# LM2678.net
KiCad netlist of a schematic drawn in Altium Designer
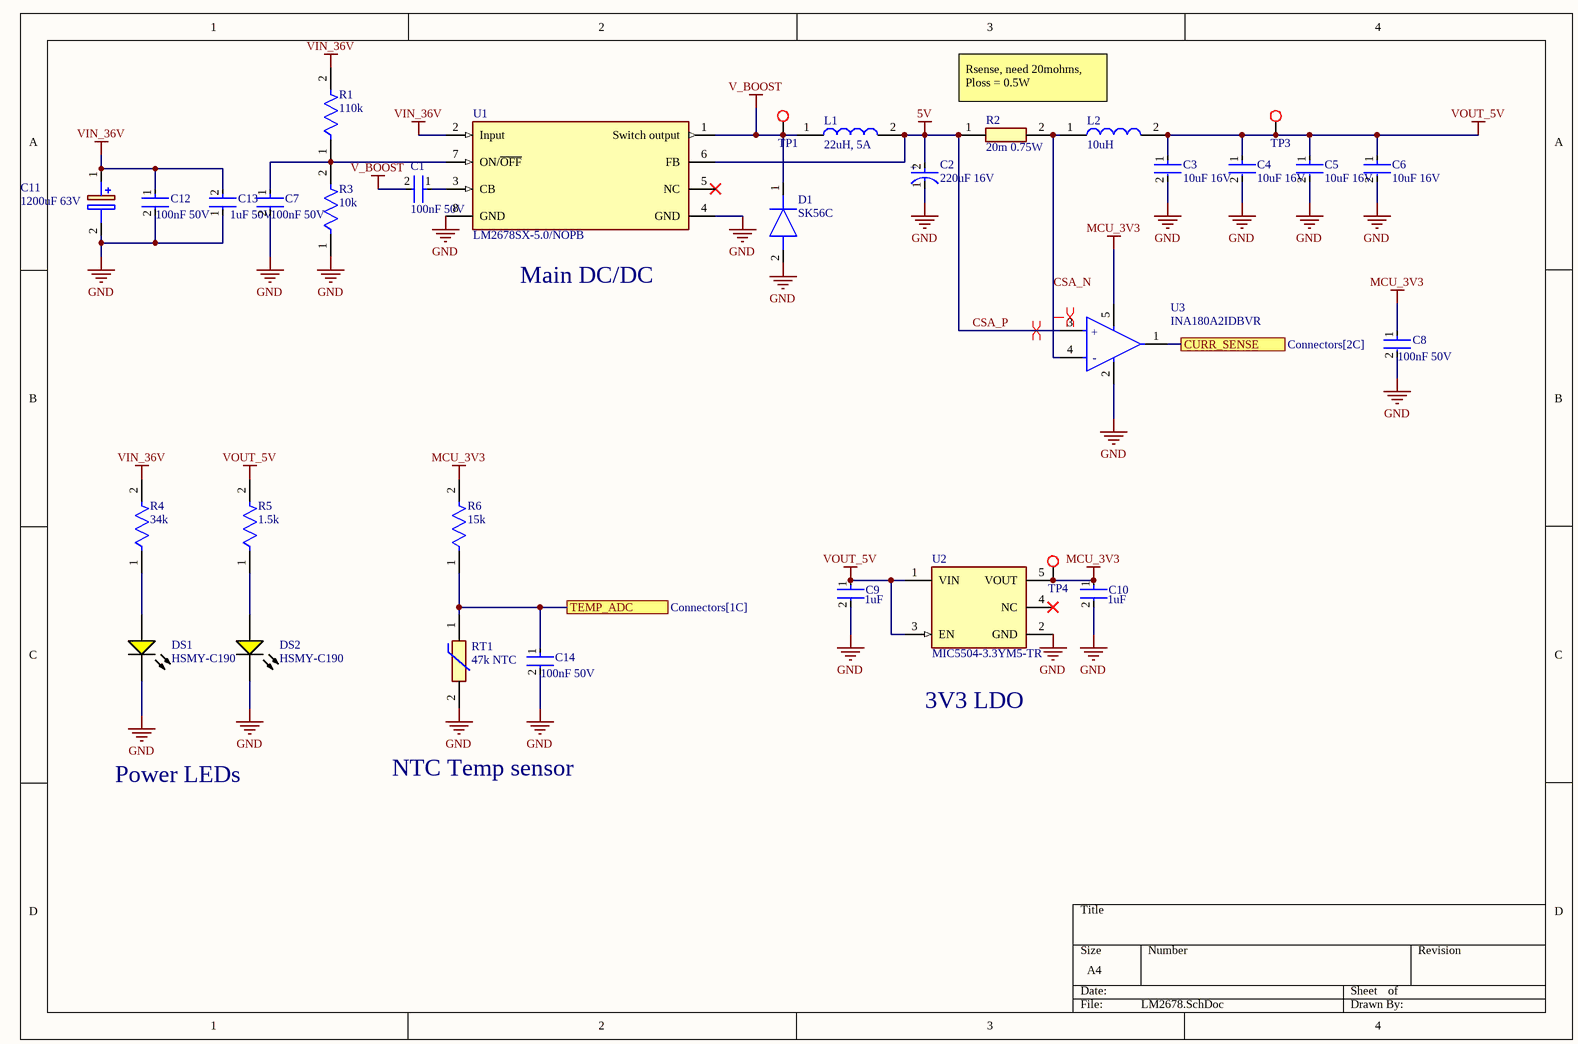
[diagram p0: LM2678.SchDoc]

(export (version "E")
  (design (tool "Eeschema 10.0.6"))
  (components
    (comp (ref "C1")
      (value "100nF 50V")
      (footprint "FP-CL31-IPC_C")
      (description "Cap Ceramic 100nF 50V X7R ±10% SMD 1206 +125°C Embossed T/R")
      (fields (field (name "TOLERANCE") "10%"))
      (libsource (lib "Altium Content Vault") (part "b4654b650e69147ec39a6b967a45e02"))
    )
    (comp (ref "C2")
      (value "220uF 16V")
      (footprint "FP-OS-CON-TH-E7-d_0_6-MFG")
      (description "CAP ALUM POLY 220UF 20% 16V T/H")
      (fields (field (name "VOLTAGE") "16V") (field (name "TOLERANCE") "20%"))
      (libsource (lib "Altium Content Vault") (part "a00bbbee19879c290e62620ae7e47b1"))
    )
    (comp (ref "C3")
      (value "10uF 16V")
      (footprint "FP-CL21-IPC_B")
      (description "CL21 Series 0805 10uF 16V ±10% Tolerance X5R Multilayer Ceramic Chip Capacitor")
      (fields (field (name "VOLTAGE") "16V") (field (name "TOLERANCE") "10%"))
      (libsource (lib "Altium Content Vault") (part "b4654b650e69147ec39a6b967a45e02"))
    )
    (comp (ref "C4")
      (value "10uF 16V")
      (footprint "FP-CL21-IPC_B")
      (description "CL21 Series 0805 10uF 16V ±10% Tolerance X5R Multilayer Ceramic Chip Capacitor")
      (fields (field (name "VOLTAGE") "16V") (field (name "TOLERANCE") "10%"))
      (libsource (lib "Altium Content Vault") (part "b4654b650e69147ec39a6b967a45e02"))
    )
    (comp (ref "C5")
      (value "10uF 16V")
      (footprint "FP-CL21-IPC_B")
      (description "CL21 Series 0805 10uF 16V ±10% Tolerance X5R Multilayer Ceramic Chip Capacitor")
      (fields (field (name "VOLTAGE") "16V") (field (name "TOLERANCE") "10%"))
      (libsource (lib "Altium Content Vault") (part "b4654b650e69147ec39a6b967a45e02"))
    )
    (comp (ref "C6")
      (value "10uF 16V")
      (footprint "FP-CL21-IPC_B")
      (description "CL21 Series 0805 10uF 16V ±10% Tolerance X5R Multilayer Ceramic Chip Capacitor")
      (fields (field (name "VOLTAGE") "16V") (field (name "TOLERANCE") "10%"))
      (libsource (lib "Altium Content Vault") (part "b4654b650e69147ec39a6b967a45e02"))
    )
    (comp (ref "C7")
      (value "100nF 50V")
      (footprint "FP-CL31-IPC_C")
      (description "Cap Ceramic 100nF 50V X7R ±10% SMD 1206 +125°C Embossed T/R")
      (fields (field (name "TOLERANCE") "10%"))
      (libsource (lib "Altium Content Vault") (part "b4654b650e69147ec39a6b967a45e02"))
    )
    (comp (ref "C8")
      (value "100nF 50V")
      (footprint "FP-CL31-IPC_C")
      (description "Cap Ceramic 100nF 50V X7R ±10% SMD 1206 +125°C Embossed T/R")
      (fields (field (name "TOLERANCE") "10%"))
      (libsource (lib "Altium Content Vault") (part "b4654b650e69147ec39a6b967a45e02"))
    )
    (comp (ref "C9")
      (value "1uF")
      (footprint "FP-CL10-IPC_C")
      (description "Cap Ceramic 1uF 10V X5R ±10% Pad SMD 0603 +85°C T/R")
      (fields (field (name "VOLTAGE") "10V") (field (name "TOLERANCE") "10%"))
      (libsource (lib "Altium Content Vault") (part "b4654b650e69147ec39a6b967a45e02"))
    )
    (comp (ref "C10")
      (value "1uF")
      (footprint "FP-CL10-IPC_C")
      (description "Cap Ceramic 1uF 10V X5R ±10% Pad SMD 0603 +85°C T/R")
      (fields (field (name "VOLTAGE") "10V") (field (name "TOLERANCE") "10%"))
      (libsource (lib "Altium Content Vault") (part "b4654b650e69147ec39a6b967a45e02"))
    )
    (comp (ref "C11")
      (value "1200uF 63V")
      (footprint "SamacSys:CAPPRD750W80D1825H3750")
      (description "Capacitor Polarised")
      (fields
        (field (name "MANUFACTURER_PART_NUMBER") "UHE1J122MHD6")
        (field (name "MOUSER PART NUMBER") "647-UHE1J122MHD6")
      )
      (libsource (lib "*") (part "UHE1J122MHD6"))
    )
    (comp (ref "C12")
      (value "100nF 50V")
      (footprint "FP-CL31-IPC_C")
      (description "Cap Ceramic 100nF 50V X7R ±10% SMD 1206 +125°C Embossed T/R")
      (fields (field (name "TOLERANCE") "10%"))
      (libsource (lib "Altium Content Vault") (part "b4654b650e69147ec39a6b967a45e02"))
    )
    (comp (ref "C13")
      (value "1uF 50V")
      (footprint "FP-C1608-080-0_1-IPC_B")
      (description "Multilayer Ceramic Capacitors 1μF ±10% 50V X5R SMD 0603")
      (fields (field (name "VOLTAGE") "50V") (field (name "TOLERANCE") "10%"))
      (libsource (lib "Altium Content Vault") (part "236180d848d6139a670b325ea6854c9"))
    )
    (comp (ref "C14")
      (value "100nF 50V")
      (footprint "FP-CL31-IPC_C")
      (description "Cap Ceramic 100nF 50V X7R ±10% SMD 1206 +125°C Embossed T/R")
      (fields (field (name "TOLERANCE") "10%"))
      (libsource (lib "Altium Content Vault") (part "b4654b650e69147ec39a6b967a45e02"))
    )
    (comp (ref "D1")
      (value "SK56C")
      (footprint "SamacSys:DIOM7959X262N")
      (description "Diode")
      (fields (field (name "MOUSER PART NUMBER") "821-SK56C"))
      (libsource (lib "*") (part "SK56C"))
    )
    (comp (ref "DS1")
      (value "HSMY-C190")
      (footprint "AVAG-HSMX-C190_V")
      (description "LED Uni-Color Yellow, 65 mW, 20 mA, -40 to 85 degC, 2-Pin SMD, RoHS, Tape and Reel")
      (fields (field (name "TOLERANCE") "1%"))
      (libsource (lib "Altium Content Vault") (part "LED-YELLOW-AK-2"))
    )
    (comp (ref "DS2")
      (value "HSMY-C190")
      (footprint "AVAG-HSMX-C190_V")
      (description "LED Uni-Color Yellow, 65 mW, 20 mA, -40 to 85 degC, 2-Pin SMD, RoHS, Tape and Reel")
      (fields (field (name "TOLERANCE") "1%"))
      (libsource (lib "Altium Content Vault") (part "LED-YELLOW-AK-2"))
    )
    (comp (ref "L1")
      (value "22uH, 5A")
      (footprint "SamacSys:AMRM00101040220MA1")
      (description "Inductor")
      (fields
        (field (name "MANUFACTURER_PART_NUMBER") "AMRM00101040220MA1")
        (field (name "MOUSER PART NUMBER") "673-AMRM101040220MA1")
      )
      (libsource (lib "*") (part "AMRM00101040220MA1"))
    )
    (comp (ref "L2")
      (value "10uH")
      (footprint "SamacSys:HPC8040NC4R7M")
      (description "Inductor")
      (fields (field (name "MANUFACTURER_PART_NUMBER") "HPC8040NC-4R7M"))
      (libsource (lib "*") (part "HPC8040NC-4R7M"))
    )
    (comp (ref "R1")
      (value "110k")
      (footprint "FP-RC2012-MFG")
      (description "Res Thick Film 0805 110kΩ 1% 0.125W ±100ppm/°C Molded SMD T/R")
      (fields (field (name "TOLERANCE") "1%"))
      (libsource (lib "Altium Content Vault") (part "1029c3af85768c4190bb7ad29bc67b5"))
    )
    (comp (ref "R2")
      (value "20m 0.75W")
      (footprint "SamacSys:RESC2114X85N")
      (description "Resistor")
      (fields (field (name "MANUFACTURER_PART_NUMBER") "D1WEL0805CR080F-T5"))
      (libsource (lib "*") (part "D1WEL0805CR080F-T5"))
    )
    (comp (ref "R3")
      (value "10k")
      (footprint "FP-MC01W0805-IPC_C")
      (description "Resistor, 10K, 0.1W, 1%, 0805, Reel")
      (fields (field (name "TOLERANCE") "1%"))
      (libsource (lib "Altium Content Vault") (part "1029c3af85768c4190bb7ad29bc67b5"))
    )
    (comp (ref "R4")
      (value "34k")
      (footprint "FP-CRCW0805-e3-IPC_B")
      (description "RES Thick Film, 34kΩ, 1%, 0.125W, 100ppm/°C, 0805")
      (fields (field (name "TOLERANCE") "1%"))
      (libsource (lib "Altium Content Vault") (part "1029c3af85768c4190bb7ad29bc67b5"))
    )
    (comp (ref "R5")
      (value "1.5k")
      (footprint "FP-RC1608-IPC_B")
      (description "Res Thick Film 0603 1.5kΩ 1% 0.1W ±100ppm/°C Molded SMD T/R")
      (fields (field (name "TOLERANCE") "1%"))
      (libsource (lib "Altium Content Vault") (part "1029c3af85768c4190bb7ad29bc67b5"))
    )
    (comp (ref "R6")
      (value "15k")
      (footprint "FP-CRCW1206-e3-IPC_B")
      (description "RES Thick Film, 15kΩ, 5%, 0.25W, 200ppm/°C, 1206")
      (fields (field (name "TOLERANCE") "5%"))
      (libsource (lib "Altium Content Vault") (part "1029c3af85768c4190bb7ad29bc67b5"))
    )
    (comp (ref "RT1")
      (value "47k NTC")
      (footprint "SamacSys:NTCLE100E3473GB0")
      (description "Thermistor")
      (fields
        (field (name "MANUFACTURER_PART_NUMBER") "NTCLE100E3473GB0")
        (field (name "MOUSER PART NUMBER") "594-NTCLE100E3473GB0")
      )
      (libsource (lib "*") (part "NTCLE100E3473GB0"))
    )
    (comp (ref "TP1") (value "TP") (footprint "Testpoint") (libsource (lib "Schlib1") (part "Testpoint")))
    (comp (ref "TP3") (value "TP") (footprint "Testpoint") (libsource (lib "Schlib1") (part "Testpoint")))
    (comp (ref "TP4") (value "TP") (footprint "Testpoint") (libsource (lib "Schlib1") (part "Testpoint")))
    (comp (ref "U1")
      (value "LM2678SX-5.0/NOPB")
      (footprint "LM2678SX-5.0/NOPB")
      (libsource (lib "Schlib1") (part "LM2678SX-5.0/NOPB"))
    )
    (comp (ref "U2")
      (value "MIC5504-3.3YM5-TR")
      (footprint "FP-SOT23-5LD-PL-1-MFG")
      (description "IC REG LINEAR 3.3V 300MA SOT23-5")
      (libsource (lib "Altium Content Vault") (part "96048095611b4a9579e1e315950d302"))
    )
    (comp (ref "U3")
      (value "INA180A2IDBVR")
      (footprint "FP-DBV0005A-MFG")
      (description "IC CURR SENSE 1 CIRCUIT SOT23-5")
      (libsource (lib "Altium Content Vault") (part "0a55cf1a948ad01a3239aec1b7efad0"))
    )
  )
  (nets
    (net (code "1") (name "/CSA_N") (class "Default")
      (node (ref "L2") (pin "1") (pinfunction "1_1") (pintype "passive"))
      (node (ref "R2") (pin "2") (pinfunction "2_2") (pintype "passive"))
      (node (ref "U3") (pin "4") (pinfunction "IN-_4") (pintype "tri_state"))
    )
    (net (code "2") (name "/CURR_SENSE") (class "Default")
      (node (ref "U3") (pin "1") (pinfunction "OUT_1") (pintype "passive"))
    )
    (net (code "3") (name "/TEMP_ADC") (class "Default")
      (node (ref "C14") (pin "1") (pinfunction "1_1") (pintype "passive"))
      (node (ref "R6") (pin "1") (pinfunction "1_1") (pintype "passive"))
      (node (ref "RT1") (pin "1") (pinfunction "1_1") (pintype "passive"))
    )
    (net (code "4") (name "5V") (class "Default")
      (node (ref "C2") (pin "2") (pinfunction "A_2") (pintype "passive"))
      (node (ref "L1") (pin "2") (pinfunction "2_2") (pintype "passive"))
      (node (ref "R2") (pin "1") (pinfunction "1_1") (pintype "passive"))
      (node (ref "U1") (pin "6") (pinfunction "FB_6") (pintype "passive"))
      (node (ref "U3") (pin "3") (pinfunction "IN+_3") (pintype "tri_state"))
    )
    (net (code "5") (name "GND") (class "Default")
      (node (ref "C10") (pin "2") (pinfunction "2_2") (pintype "passive"))
      (node (ref "C11") (pin "2") (pinfunction "-_2") (pintype "passive"))
      (node (ref "C12") (pin "2") (pinfunction "2_2") (pintype "passive"))
      (node (ref "C13") (pin "1") (pinfunction "1_1") (pintype "passive"))
      (node (ref "C14") (pin "2") (pinfunction "2_2") (pintype "passive"))
      (node (ref "C2") (pin "1") (pinfunction "C_1") (pintype "passive"))
      (node (ref "C3") (pin "2") (pinfunction "2_2") (pintype "passive"))
      (node (ref "C4") (pin "2") (pinfunction "2_2") (pintype "passive"))
      (node (ref "C5") (pin "2") (pinfunction "2_2") (pintype "passive"))
      (node (ref "C6") (pin "2") (pinfunction "2_2") (pintype "passive"))
      (node (ref "C7") (pin "2") (pinfunction "2_2") (pintype "passive"))
      (node (ref "C8") (pin "2") (pinfunction "2_2") (pintype "passive"))
      (node (ref "C9") (pin "2") (pinfunction "2_2") (pintype "passive"))
      (node (ref "D1") (pin "2") (pinfunction "A_2") (pintype "passive"))
      (node (ref "DS1") (pin "2") (pinfunction "K_2") (pintype "passive"))
      (node (ref "DS2") (pin "2") (pinfunction "K_2") (pintype "passive"))
      (node (ref "R3") (pin "1") (pinfunction "1_1") (pintype "passive"))
      (node (ref "RT1") (pin "2") (pinfunction "2_2") (pintype "passive"))
      (node (ref "U1") (pin "4") (pinfunction "GND_4") (pintype "power_in"))
      (node (ref "U1") (pin "8") (pinfunction "GND_8") (pintype "passive"))
      (node (ref "U2") (pin "2") (pinfunction "GND_2") (pintype "power_in"))
      (node (ref "U3") (pin "2") (pinfunction "GND_2") (pintype "power_in"))
    )
    (net (code "6") (name "MCU_3V3") (class "Default")
      (node (ref "C10") (pin "1") (pinfunction "1_1") (pintype "passive"))
      (node (ref "C8") (pin "1") (pinfunction "1_1") (pintype "passive"))
      (node (ref "R6") (pin "2") (pinfunction "2_2") (pintype "passive"))
      (node (ref "TP4") (pin "0") (pinfunction "0_0") (pintype "passive"))
      (node (ref "U2") (pin "5") (pinfunction "VOUT_5") (pintype "power_in"))
      (node (ref "U3") (pin "5") (pinfunction "VS_5") (pintype "power_in"))
    )
    (net (code "7") (name "Net-(DS1-A)") (class "Default")
      (node (ref "DS1") (pin "1") (pinfunction "A_1") (pintype "passive"))
      (node (ref "R4") (pin "1") (pinfunction "1_1") (pintype "passive"))
    )
    (net (code "8") (name "Net-(DS2-A)") (class "Default")
      (node (ref "DS2") (pin "1") (pinfunction "A_1") (pintype "passive"))
      (node (ref "R5") (pin "1") (pinfunction "1_1") (pintype "passive"))
    )
    (net (code "9") (name "Net-(U1-CB)") (class "Default")
      (node (ref "C1") (pin "1") (pinfunction "1_1") (pintype "passive"))
      (node (ref "U1") (pin "3") (pinfunction "CB_3") (pintype "input"))
    )
    (net (code "10") (name "Net-(U1-ON{slash}~{OFF})") (class "Default")
      (node (ref "C7") (pin "1") (pinfunction "1_1") (pintype "passive"))
      (node (ref "R1") (pin "1") (pinfunction "1_1") (pintype "passive"))
      (node (ref "R3") (pin "2") (pinfunction "2_2") (pintype "passive"))
      (node (ref "U1") (pin "7") (pinfunction "ON/~{OFF}_7") (pintype "input"))
    )
    (net (code "11") (name "VIN_36V") (class "Default")
      (node (ref "C11") (pin "1") (pinfunction "+_1") (pintype "passive"))
      (node (ref "C12") (pin "1") (pinfunction "1_1") (pintype "passive"))
      (node (ref "C13") (pin "2") (pinfunction "2_2") (pintype "passive"))
      (node (ref "R1") (pin "2") (pinfunction "2_2") (pintype "passive"))
      (node (ref "R4") (pin "2") (pinfunction "2_2") (pintype "passive"))
      (node (ref "U1") (pin "2") (pinfunction "Input_2") (pintype "input"))
    )
    (net (code "12") (name "VOUT_5V") (class "Default")
      (node (ref "C3") (pin "1") (pinfunction "1_1") (pintype "passive"))
      (node (ref "C4") (pin "1") (pinfunction "1_1") (pintype "passive"))
      (node (ref "C5") (pin "1") (pinfunction "1_1") (pintype "passive"))
      (node (ref "C6") (pin "1") (pinfunction "1_1") (pintype "passive"))
      (node (ref "C9") (pin "1") (pinfunction "1_1") (pintype "passive"))
      (node (ref "L2") (pin "2") (pinfunction "2_2") (pintype "passive"))
      (node (ref "R5") (pin "2") (pinfunction "2_2") (pintype "passive"))
      (node (ref "TP3") (pin "0") (pinfunction "0_0") (pintype "passive"))
      (node (ref "U2") (pin "1") (pinfunction "VIN_1") (pintype "power_in"))
      (node (ref "U2") (pin "3") (pinfunction "EN_3") (pintype "input"))
    )
    (net (code "13") (name "V_BOOST") (class "Default")
      (node (ref "C1") (pin "2") (pinfunction "2_2") (pintype "passive"))
      (node (ref "D1") (pin "1") (pinfunction "K_1") (pintype "passive"))
      (node (ref "L1") (pin "1") (pinfunction "1_1") (pintype "passive"))
      (node (ref "TP1") (pin "0") (pinfunction "0_0") (pintype "passive"))
      (node (ref "U1") (pin "1") (pinfunction "Switch_output_1") (pintype "output"))
    )
    (net (code "14") (name "unconnected-(U1-NC-Pad5)") (class "Default")
      (node (ref "U1") (pin "5") (pinfunction "NC_5") (pintype "passive+no_connect"))
    )
    (net (code "15") (name "unconnected-(U2-NC-Pad4)") (class "Default")
      (node (ref "U2") (pin "4") (pinfunction "NC_4") (pintype "passive+no_connect"))
    )
  )
)
